# dab_mainboard.net
KiCad netlist of a schematic drawn in EAGLE
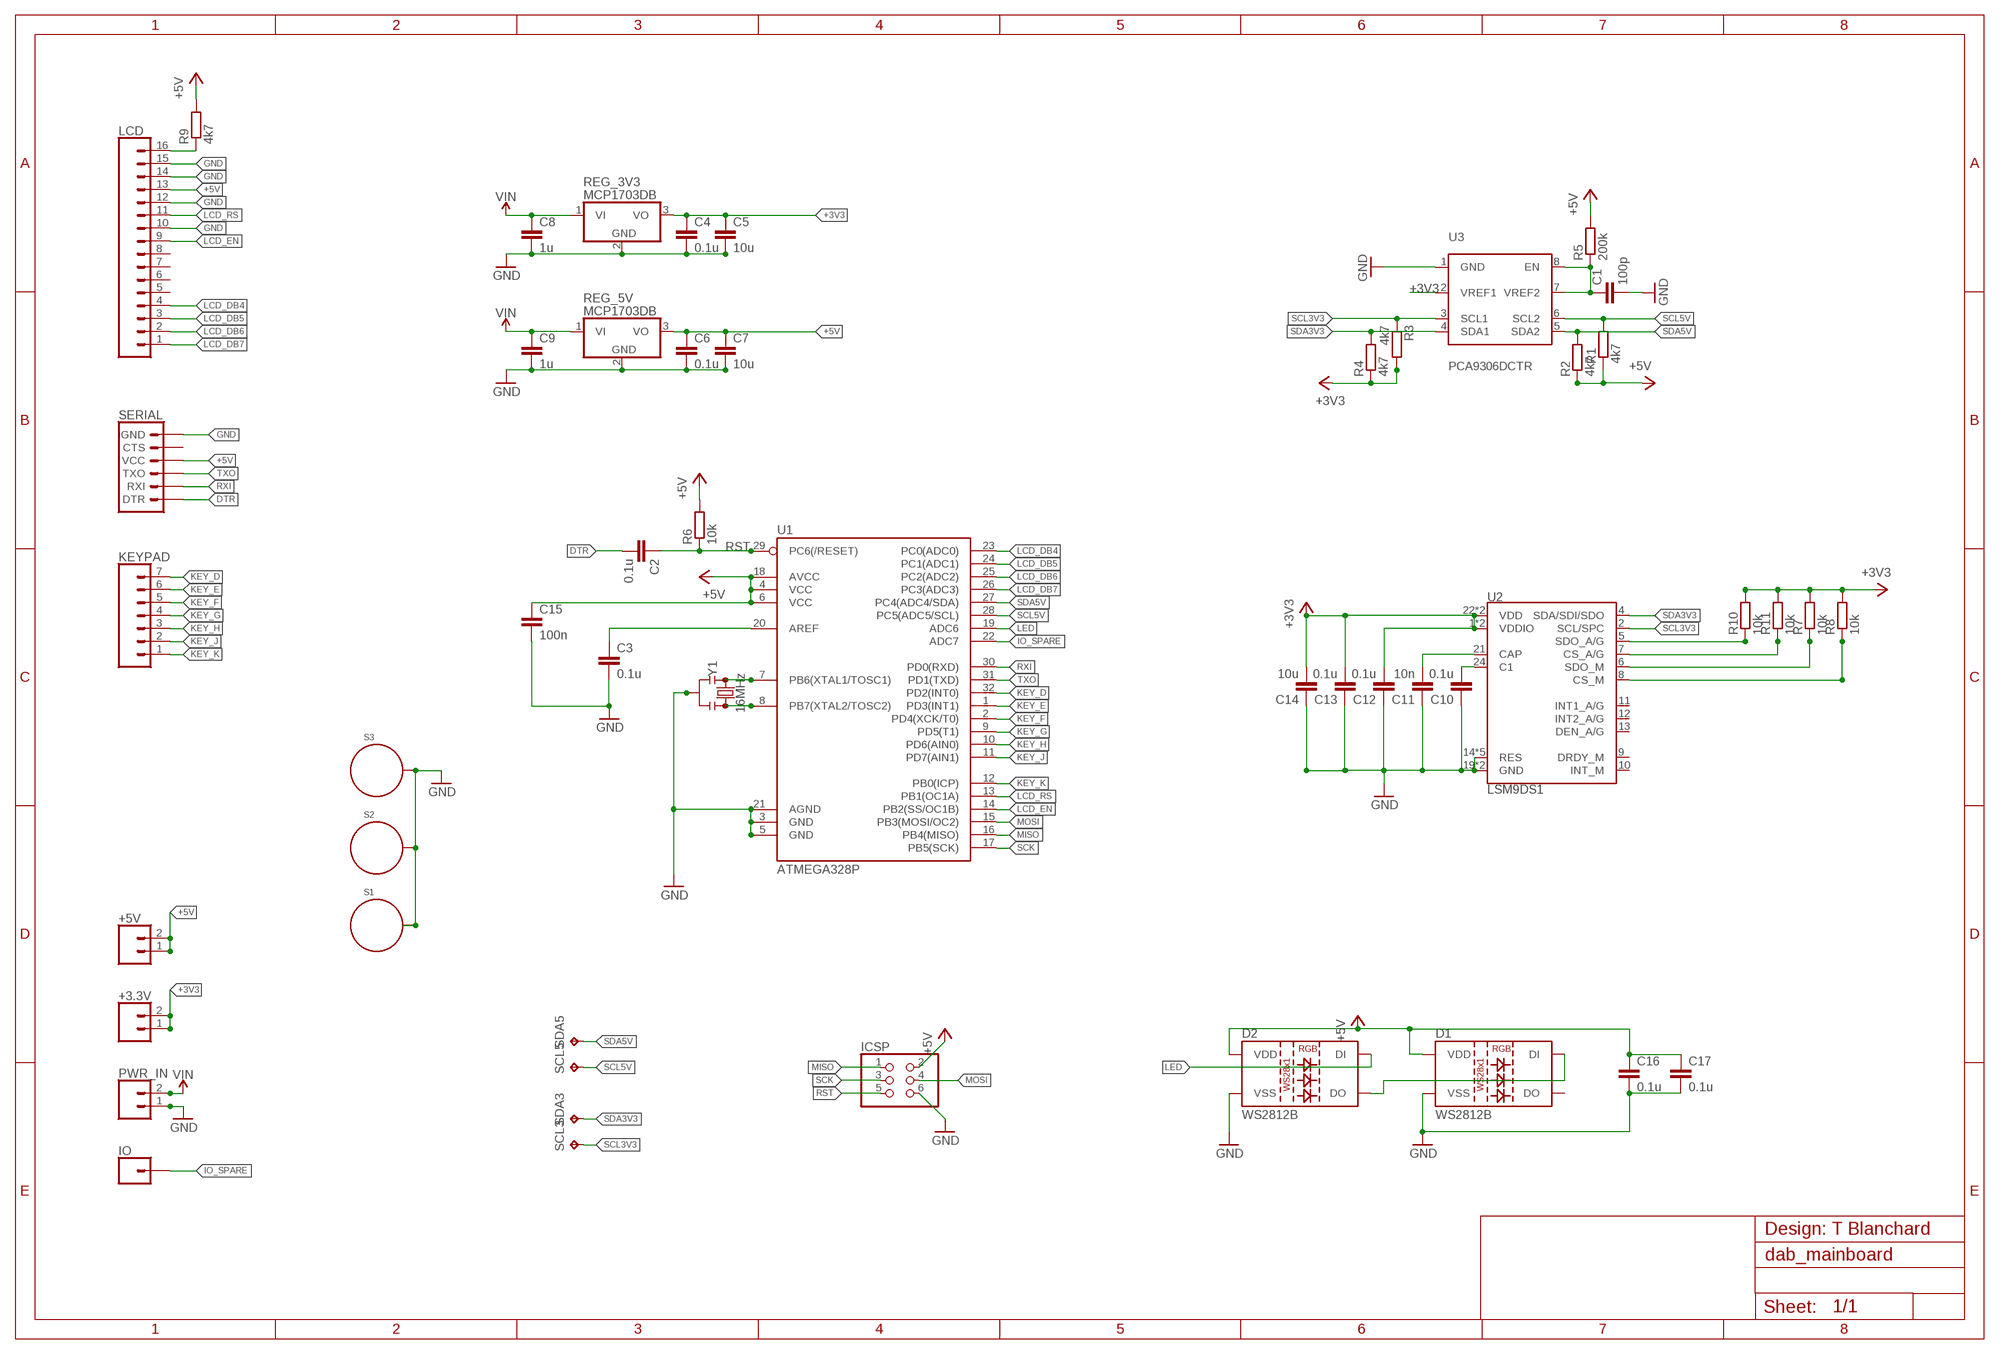
[diagram p0: schematic, sheet 1]

(export (version "E")
  (design (tool "Eeschema 10.0.6"))
  (components
    (comp (ref "+3.3V")
      (value "CONN_02")
      (footprint "eagle-import:1X02")
      (libsource (lib "eagle-import") (part "CONN_02"))
    )
    (comp (ref "+5V")
      (value "CONN_02")
      (footprint "eagle-import:1X02")
      (libsource (lib "eagle-import") (part "CONN_02"))
    )
    (comp (ref "C1")
      (value "100p")
      (footprint "eagle-import:C0603")
      (libsource (lib "eagle-import") (part "C-EUC0603"))
    )
    (comp (ref "C2")
      (value "0.1u")
      (footprint "eagle-import:C0603")
      (libsource (lib "eagle-import") (part "C-EUC0603"))
    )
    (comp (ref "C3")
      (value "0.1u")
      (footprint "eagle-import:C0603")
      (libsource (lib "eagle-import") (part "C-EUC0603"))
    )
    (comp (ref "C4")
      (value "0.1u")
      (footprint "eagle-import:C0603")
      (libsource (lib "eagle-import") (part "C-EUC0603"))
    )
    (comp (ref "C5")
      (value "10u")
      (footprint "eagle-import:C0805")
      (libsource (lib "eagle-import") (part "C-EUC0805"))
    )
    (comp (ref "C6")
      (value "0.1u")
      (footprint "eagle-import:C0603")
      (libsource (lib "eagle-import") (part "C-EUC0603"))
    )
    (comp (ref "C7")
      (value "10u")
      (footprint "eagle-import:C0805")
      (libsource (lib "eagle-import") (part "C-EUC0805"))
    )
    (comp (ref "C8")
      (value "1u")
      (footprint "eagle-import:C0603")
      (libsource (lib "eagle-import") (part "C-EUC0603"))
    )
    (comp (ref "C9")
      (value "1u")
      (footprint "eagle-import:C0603")
      (libsource (lib "eagle-import") (part "C-EUC0603"))
    )
    (comp (ref "C10")
      (value "0.1u")
      (footprint "eagle-import:C0603")
      (libsource (lib "eagle-import") (part "C-EUC0603"))
    )
    (comp (ref "C11")
      (value "10n")
      (footprint "eagle-import:C0603")
      (libsource (lib "eagle-import") (part "C-EUC0603"))
    )
    (comp (ref "C12")
      (value "0.1u")
      (footprint "eagle-import:C0603")
      (libsource (lib "eagle-import") (part "C-EUC0603"))
    )
    (comp (ref "C13")
      (value "0.1u")
      (footprint "eagle-import:C0603")
      (libsource (lib "eagle-import") (part "C-EUC0603"))
    )
    (comp (ref "C14")
      (value "10u")
      (footprint "eagle-import:C0603")
      (libsource (lib "eagle-import") (part "C-EUC0603"))
    )
    (comp (ref "C15")
      (value "100n")
      (footprint "eagle-import:C0603")
      (libsource (lib "eagle-import") (part "C-EUC0603"))
    )
    (comp (ref "C16")
      (value "0.1u")
      (footprint "eagle-import:C0603")
      (libsource (lib "eagle-import") (part "C-EUC0603"))
    )
    (comp (ref "C17")
      (value "0.1u")
      (footprint "eagle-import:C0603")
      (libsource (lib "eagle-import") (part "C-EUC0603"))
    )
    (comp (ref "D1")
      (value "WS2812B")
      (footprint "eagle-import:WS2812B")
      (libsource (lib "eagle-import") (part "WS2812B"))
    )
    (comp (ref "D2")
      (value "WS2812B")
      (footprint "eagle-import:WS2812B")
      (libsource (lib "eagle-import") (part "WS2812B"))
    )
    (comp (ref "ICSP")
      (value "PINHD-2X3")
      (footprint "eagle-import:2X03")
      (libsource (lib "eagle-import") (part "PINHD-2X3"))
    )
    (comp (ref "IO")
      (value "CONN_01")
      (footprint "eagle-import:1X01")
      (libsource (lib "eagle-import") (part "CONN_01"))
    )
    (comp (ref "KEYPAD")
      (value "CONN_07")
      (footprint "eagle-import:1X07")
      (libsource (lib "eagle-import") (part "CONN_07"))
    )
    (comp (ref "LCD")
      (value "CONN_16")
      (footprint "eagle-import:1X16")
      (libsource (lib "eagle-import") (part "CONN_16"))
    )
    (comp (ref "PWR_IN")
      (value "CONN_02")
      (footprint "eagle-import:1X02")
      (libsource (lib "eagle-import") (part "CONN_02"))
    )
    (comp (ref "R1")
      (value "4k7")
      (footprint "eagle-import:R0603")
      (libsource (lib "eagle-import") (part "R-EU_R0603"))
    )
    (comp (ref "R2")
      (value "4k7")
      (footprint "eagle-import:R0603")
      (libsource (lib "eagle-import") (part "R-EU_R0603"))
    )
    (comp (ref "R3")
      (value "4k7")
      (footprint "eagle-import:R0603")
      (libsource (lib "eagle-import") (part "R-EU_R0603"))
    )
    (comp (ref "R4")
      (value "4k7")
      (footprint "eagle-import:R0603")
      (libsource (lib "eagle-import") (part "R-EU_R0603"))
    )
    (comp (ref "R5")
      (value "200k")
      (footprint "eagle-import:R0603")
      (libsource (lib "eagle-import") (part "R-EU_R0603"))
    )
    (comp (ref "R6")
      (value "10k")
      (footprint "eagle-import:R0603")
      (libsource (lib "eagle-import") (part "R-EU_R0603"))
    )
    (comp (ref "R7")
      (value "10k")
      (footprint "eagle-import:R0603")
      (libsource (lib "eagle-import") (part "R-EU_R0603"))
    )
    (comp (ref "R8")
      (value "10k")
      (footprint "eagle-import:R0603")
      (libsource (lib "eagle-import") (part "R-EU_R0603"))
    )
    (comp (ref "R9")
      (value "4k7")
      (footprint "eagle-import:R0603")
      (libsource (lib "eagle-import") (part "R-EU_R0603"))
    )
    (comp (ref "R10")
      (value "10k")
      (footprint "eagle-import:R0603")
      (libsource (lib "eagle-import") (part "R-EU_R0603"))
    )
    (comp (ref "R11")
      (value "10k")
      (footprint "eagle-import:R0603")
      (libsource (lib "eagle-import") (part "R-EU_R0603"))
    )
    (comp (ref "REG_3V3")
      (value "MCP1703DB")
      (footprint "eagle-import:SOT223")
      (libsource (lib "eagle-import") (part "MCP1703DB"))
    )
    (comp (ref "REG_5V")
      (value "MCP1703DB")
      (footprint "eagle-import:SOT223")
      (libsource (lib "eagle-import") (part "MCP1703DB"))
    )
    (comp (ref "S1")
      (value "STANDOFF_ELECTRICAL")
      (footprint "eagle-import:STANDOFF-ELECTRICAL")
      (libsource (lib "eagle-import") (part "STANDOFF_ELECTRICAL"))
    )
    (comp (ref "S2")
      (value "STANDOFF_ELECTRICAL")
      (footprint "eagle-import:STANDOFF-ELECTRICAL")
      (libsource (lib "eagle-import") (part "STANDOFF_ELECTRICAL"))
    )
    (comp (ref "S3")
      (value "STANDOFF_ELECTRICAL")
      (footprint "eagle-import:STANDOFF-ELECTRICAL")
      (libsource (lib "eagle-import") (part "STANDOFF_ELECTRICAL"))
    )
    (comp (ref "SCL3")
      (value "TPTP08R")
      (footprint "eagle-import:TP08R")
      (libsource (lib "eagle-import") (part "TPTP08R"))
    )
    (comp (ref "SCL5")
      (value "TPTP08R")
      (footprint "eagle-import:TP08R")
      (libsource (lib "eagle-import") (part "TPTP08R"))
    )
    (comp (ref "SDA3")
      (value "TPTP08R")
      (footprint "eagle-import:TP08R")
      (libsource (lib "eagle-import") (part "TPTP08R"))
    )
    (comp (ref "SDA5")
      (value "TPTP08R")
      (footprint "eagle-import:TP08R")
      (libsource (lib "eagle-import") (part "TPTP08R"))
    )
    (comp (ref "SERIAL")
      (value "6_PIN_SERIAL_TARGETSILK")
      (footprint "eagle-import:6_PIN_SERIAL_TARGET_SIDE_W_SILK")
      (libsource (lib "eagle-import") (part "6_PIN_SERIAL_TARGETSILK"))
    )
    (comp (ref "U1")
      (value "ATMEGA328P")
      (footprint "eagle-import:TQFP32-08")
      (libsource (lib "eagle-import") (part "ATMEGA328P_TQFP"))
    )
    (comp (ref "U2")
      (value "LSM9DS1")
      (footprint "eagle-import:LGA-24-3.5X3")
      (libsource (lib "eagle-import") (part "LSM9DS1"))
    )
    (comp (ref "U3")
      (value "PCA9306DCTR")
      (footprint "eagle-import:SM8")
      (libsource (lib "eagle-import") (part "PCA9306DCTR"))
    )
    (comp (ref "Y1")
      (value "16MHz")
      (footprint "eagle-import:RESONATOR-SMD-3.2X1.3")
      (libsource (lib "eagle-import") (part "RESONATOR-16MHZSMD_3.2X1.3"))
    )
  )
  (nets
    (net (code "1") (name "+3V3") (class "Default")
      (node (ref "+3.3V") (pin "1") (pinfunction "1_1") (pintype "passive"))
      (node (ref "+3.3V") (pin "2") (pinfunction "2_2") (pintype "passive"))
      (node (ref "C12") (pin "2") (pinfunction "2_2") (pintype "passive"))
      (node (ref "C13") (pin "2") (pinfunction "2_2") (pintype "passive"))
      (node (ref "C14") (pin "2") (pinfunction "2_2") (pintype "passive"))
      (node (ref "C4") (pin "1") (pinfunction "1_1") (pintype "passive"))
      (node (ref "C5") (pin "1") (pinfunction "1_1") (pintype "passive"))
      (node (ref "R10") (pin "2") (pinfunction "2_2") (pintype "passive"))
      (node (ref "R11") (pin "2") (pinfunction "2_2") (pintype "passive"))
      (node (ref "R3") (pin "2") (pinfunction "2_2") (pintype "passive"))
      (node (ref "R4") (pin "1") (pinfunction "1_1") (pintype "passive"))
      (node (ref "R7") (pin "2") (pinfunction "2_2") (pintype "passive"))
      (node (ref "R8") (pin "2") (pinfunction "2_2") (pintype "passive"))
      (node (ref "REG_3V3") (pin "3") (pinfunction "VO_3") (pintype "passive"))
      (node (ref "U2") (pin "1") (pinfunction "VDDIO_1") (pintype "bidirectional"))
      (node (ref "U2") (pin "22") (pinfunction "VDD_22") (pintype "bidirectional"))
      (node (ref "U2") (pin "23") (pinfunction "VDD_23") (pintype "bidirectional"))
      (node (ref "U2") (pin "3") (pinfunction "VDDIO_3") (pintype "bidirectional"))
      (node (ref "U3") (pin "2") (pinfunction "VREF1_2") (pintype "power_in"))
    )
    (net (code "2") (name "+5V") (class "Default")
      (node (ref "+5V") (pin "1") (pinfunction "1_1") (pintype "passive"))
      (node (ref "+5V") (pin "2") (pinfunction "2_2") (pintype "passive"))
      (node (ref "C15") (pin "1") (pinfunction "1_1") (pintype "passive"))
      (node (ref "C16") (pin "1") (pinfunction "1_1") (pintype "passive"))
      (node (ref "C17") (pin "1") (pinfunction "1_1") (pintype "passive"))
      (node (ref "C6") (pin "1") (pinfunction "1_1") (pintype "passive"))
      (node (ref "C7") (pin "1") (pinfunction "1_1") (pintype "passive"))
      (node (ref "D1") (pin "1") (pinfunction "VDD_1") (pintype "bidirectional"))
      (node (ref "D2") (pin "1") (pinfunction "VDD_1") (pintype "bidirectional"))
      (node (ref "ICSP") (pin "2") (pinfunction "2_2") (pintype "passive"))
      (node (ref "LCD") (pin "13") (pinfunction "13_13") (pintype "passive"))
      (node (ref "R1") (pin "1") (pinfunction "1_1") (pintype "passive"))
      (node (ref "R2") (pin "1") (pinfunction "1_1") (pintype "passive"))
      (node (ref "R5") (pin "2") (pinfunction "2_2") (pintype "passive"))
      (node (ref "R6") (pin "2") (pinfunction "2_2") (pintype "passive"))
      (node (ref "R9") (pin "2") (pinfunction "2_2") (pintype "passive"))
      (node (ref "REG_5V") (pin "3") (pinfunction "VO_3") (pintype "passive"))
      (node (ref "SERIAL") (pin "P$4") (pinfunction "VCC_P$4") (pintype "passive"))
      (node (ref "U1") (pin "18") (pinfunction "AVCC_18") (pintype "bidirectional"))
      (node (ref "U1") (pin "4") (pinfunction "VCC_4") (pintype "bidirectional"))
      (node (ref "U1") (pin "6") (pinfunction "VCC_6") (pintype "bidirectional"))
    )
    (net (code "3") (name "DTR") (class "Default")
      (node (ref "C2") (pin "2") (pinfunction "2_2") (pintype "passive"))
      (node (ref "SERIAL") (pin "P$1") (pinfunction "DTR_P$1") (pintype "passive"))
    )
    (net (code "4") (name "GND") (class "Default")
      (node (ref "C1") (pin "2") (pinfunction "2_2") (pintype "passive"))
      (node (ref "C10") (pin "1") (pinfunction "1_1") (pintype "passive"))
      (node (ref "C11") (pin "1") (pinfunction "1_1") (pintype "passive"))
      (node (ref "C12") (pin "1") (pinfunction "1_1") (pintype "passive"))
      (node (ref "C13") (pin "1") (pinfunction "1_1") (pintype "passive"))
      (node (ref "C14") (pin "1") (pinfunction "1_1") (pintype "passive"))
      (node (ref "C15") (pin "2") (pinfunction "2_2") (pintype "passive"))
      (node (ref "C16") (pin "2") (pinfunction "2_2") (pintype "passive"))
      (node (ref "C17") (pin "2") (pinfunction "2_2") (pintype "passive"))
      (node (ref "C3") (pin "2") (pinfunction "2_2") (pintype "passive"))
      (node (ref "C4") (pin "2") (pinfunction "2_2") (pintype "passive"))
      (node (ref "C5") (pin "2") (pinfunction "2_2") (pintype "passive"))
      (node (ref "C6") (pin "2") (pinfunction "2_2") (pintype "passive"))
      (node (ref "C7") (pin "2") (pinfunction "2_2") (pintype "passive"))
      (node (ref "C8") (pin "2") (pinfunction "2_2") (pintype "passive"))
      (node (ref "C9") (pin "2") (pinfunction "2_2") (pintype "passive"))
      (node (ref "D1") (pin "3") (pinfunction "VSS_3") (pintype "bidirectional"))
      (node (ref "D2") (pin "3") (pinfunction "VSS_3") (pintype "bidirectional"))
      (node (ref "ICSP") (pin "6") (pinfunction "6_6") (pintype "passive"))
      (node (ref "LCD") (pin "10") (pinfunction "10_10") (pintype "passive"))
      (node (ref "LCD") (pin "12") (pinfunction "12_12") (pintype "passive"))
      (node (ref "LCD") (pin "14") (pinfunction "14_14") (pintype "passive"))
      (node (ref "LCD") (pin "15") (pinfunction "15_15") (pintype "passive"))
      (node (ref "PWR_IN") (pin "1") (pinfunction "1_1") (pintype "passive"))
      (node (ref "REG_3V3") (pin "2") (pinfunction "GND_2") (pintype "passive"))
      (node (ref "REG_5V") (pin "2") (pinfunction "GND_2") (pintype "passive"))
      (node (ref "S1") (pin "P1") (pinfunction "P$1_P1") (pintype "bidirectional"))
      (node (ref "S2") (pin "P1") (pinfunction "P$1_P1") (pintype "bidirectional"))
      (node (ref "S3") (pin "P1") (pinfunction "P$1_P1") (pintype "bidirectional"))
      (node (ref "SERIAL") (pin "P$6") (pinfunction "GND_P$6") (pintype "passive"))
      (node (ref "U1") (pin "21") (pinfunction "AGND_21") (pintype "bidirectional"))
      (node (ref "U1") (pin "3") (pinfunction "GND_3") (pintype "bidirectional"))
      (node (ref "U1") (pin "5") (pinfunction "GND_5") (pintype "bidirectional"))
      (node (ref "U2") (pin "14") (pinfunction "RES_14") (pintype "bidirectional"))
      (node (ref "U2") (pin "15") (pinfunction "RES_15") (pintype "bidirectional"))
      (node (ref "U2") (pin "16") (pinfunction "RES_16") (pintype "bidirectional"))
      (node (ref "U2") (pin "17") (pinfunction "RES_17") (pintype "bidirectional"))
      (node (ref "U2") (pin "18") (pinfunction "RES_18") (pintype "bidirectional"))
      (node (ref "U2") (pin "19") (pinfunction "GND_19") (pintype "bidirectional"))
      (node (ref "U2") (pin "20") (pinfunction "GND_20") (pintype "bidirectional"))
      (node (ref "U3") (pin "1") (pinfunction "GND_1") (pintype "power_in"))
      (node (ref "Y1") (pin "2") (pinfunction "2_2") (pintype "passive"))
    )
    (net (code "5") (name "IO_SPARE") (class "Default")
      (node (ref "IO") (pin "1") (pinfunction "1_1") (pintype "passive"))
      (node (ref "U1") (pin "22") (pinfunction "ADC7_22") (pintype "bidirectional"))
    )
    (net (code "6") (name "KEY_D") (class "Default")
      (node (ref "KEYPAD") (pin "7") (pinfunction "7_7") (pintype "passive"))
      (node (ref "U1") (pin "32") (pinfunction "PD2(INT0)_32") (pintype "bidirectional"))
    )
    (net (code "7") (name "KEY_E") (class "Default")
      (node (ref "KEYPAD") (pin "6") (pinfunction "6_6") (pintype "passive"))
      (node (ref "U1") (pin "1") (pinfunction "PD3(INT1)_1") (pintype "bidirectional"))
    )
    (net (code "8") (name "KEY_F") (class "Default")
      (node (ref "KEYPAD") (pin "5") (pinfunction "5_5") (pintype "passive"))
      (node (ref "U1") (pin "2") (pinfunction "PD4(XCK/T0)_2") (pintype "bidirectional"))
    )
    (net (code "9") (name "KEY_G") (class "Default")
      (node (ref "KEYPAD") (pin "4") (pinfunction "4_4") (pintype "passive"))
      (node (ref "U1") (pin "9") (pinfunction "PD5(T1)_9") (pintype "bidirectional"))
    )
    (net (code "10") (name "KEY_H") (class "Default")
      (node (ref "KEYPAD") (pin "3") (pinfunction "3_3") (pintype "passive"))
      (node (ref "U1") (pin "10") (pinfunction "PD6(AIN0)_10") (pintype "bidirectional"))
    )
    (net (code "11") (name "KEY_J") (class "Default")
      (node (ref "KEYPAD") (pin "2") (pinfunction "2_2") (pintype "passive"))
      (node (ref "U1") (pin "11") (pinfunction "PD7(AIN1)_11") (pintype "bidirectional"))
    )
    (net (code "12") (name "KEY_K") (class "Default")
      (node (ref "KEYPAD") (pin "1") (pinfunction "1_1") (pintype "passive"))
      (node (ref "U1") (pin "12") (pinfunction "PB0(ICP)_12") (pintype "bidirectional"))
    )
    (net (code "13") (name "LCD_DB4") (class "Default")
      (node (ref "LCD") (pin "4") (pinfunction "4_4") (pintype "passive"))
      (node (ref "U1") (pin "23") (pinfunction "PC0(ADC0)_23") (pintype "bidirectional"))
    )
    (net (code "14") (name "LCD_DB5") (class "Default")
      (node (ref "LCD") (pin "3") (pinfunction "3_3") (pintype "passive"))
      (node (ref "U1") (pin "24") (pinfunction "PC1(ADC1)_24") (pintype "bidirectional"))
    )
    (net (code "15") (name "LCD_DB6") (class "Default")
      (node (ref "LCD") (pin "2") (pinfunction "2_2") (pintype "passive"))
      (node (ref "U1") (pin "25") (pinfunction "PC2(ADC2)_25") (pintype "bidirectional"))
    )
    (net (code "16") (name "LCD_DB7") (class "Default")
      (node (ref "LCD") (pin "1") (pinfunction "1_1") (pintype "passive"))
      (node (ref "U1") (pin "26") (pinfunction "PC3(ADC3)_26") (pintype "bidirectional"))
    )
    (net (code "17") (name "LCD_EN") (class "Default")
      (node (ref "LCD") (pin "9") (pinfunction "9_9") (pintype "passive"))
      (node (ref "U1") (pin "14") (pinfunction "PB2(SS/OC1B)_14") (pintype "bidirectional"))
    )
    (net (code "18") (name "LCD_RS") (class "Default")
      (node (ref "LCD") (pin "11") (pinfunction "11_11") (pintype "passive"))
      (node (ref "U1") (pin "13") (pinfunction "PB1(OC1A)_13") (pintype "bidirectional"))
    )
    (net (code "19") (name "LED") (class "Default")
      (node (ref "D2") (pin "4") (pinfunction "DI_4") (pintype "bidirectional"))
      (node (ref "U1") (pin "19") (pinfunction "ADC6_19") (pintype "bidirectional"))
    )
    (net (code "20") (name "MISO") (class "Default")
      (node (ref "ICSP") (pin "1") (pinfunction "1_1") (pintype "passive"))
      (node (ref "U1") (pin "16") (pinfunction "PB4(MISO)_16") (pintype "bidirectional"))
    )
    (net (code "21") (name "MOSI") (class "Default")
      (node (ref "ICSP") (pin "4") (pinfunction "4_4") (pintype "passive"))
      (node (ref "U1") (pin "15") (pinfunction "PB3(MOSI/OC2)_15") (pintype "bidirectional"))
    )
    (net (code "22") (name "Net-(D1-DI)") (class "Default")
      (node (ref "D1") (pin "4") (pinfunction "DI_4") (pintype "bidirectional"))
      (node (ref "D2") (pin "2") (pinfunction "DO_2") (pintype "bidirectional"))
    )
    (net (code "23") (name "Net-(LCD-Pad16)") (class "Default")
      (node (ref "LCD") (pin "16") (pinfunction "16_16") (pintype "passive"))
      (node (ref "R9") (pin "1") (pinfunction "1_1") (pintype "passive"))
    )
    (net (code "24") (name "Net-(U1-AREF)") (class "Default")
      (node (ref "C3") (pin "1") (pinfunction "1_1") (pintype "passive"))
      (node (ref "U1") (pin "20") (pinfunction "AREF_20") (pintype "bidirectional"))
    )
    (net (code "25") (name "Net-(U1-PB6(XTAL1{slash}TOSC1))") (class "Default")
      (node (ref "U1") (pin "7") (pinfunction "PB6(XTAL1/TOSC1)_7") (pintype "bidirectional"))
      (node (ref "Y1") (pin "1") (pinfunction "1_1") (pintype "passive"))
    )
    (net (code "26") (name "Net-(U1-PB7(XTAL2{slash}TOSC2))") (class "Default")
      (node (ref "U1") (pin "8") (pinfunction "PB7(XTAL2/TOSC2)_8") (pintype "bidirectional"))
      (node (ref "Y1") (pin "3") (pinfunction "3_3") (pintype "passive"))
    )
    (net (code "27") (name "Net-(U2-C1)") (class "Default")
      (node (ref "C10") (pin "2") (pinfunction "2_2") (pintype "passive"))
      (node (ref "U2") (pin "24") (pinfunction "C1_24") (pintype "bidirectional"))
    )
    (net (code "28") (name "Net-(U2-CAP)") (class "Default")
      (node (ref "C11") (pin "2") (pinfunction "2_2") (pintype "passive"))
      (node (ref "U2") (pin "21") (pinfunction "CAP_21") (pintype "bidirectional"))
    )
    (net (code "29") (name "Net-(U2-CS_A{slash}G)") (class "Default")
      (node (ref "R11") (pin "1") (pinfunction "1_1") (pintype "passive"))
      (node (ref "U2") (pin "7") (pinfunction "CS_A/G_7") (pintype "bidirectional"))
    )
    (net (code "30") (name "Net-(U2-CS_M)") (class "Default")
      (node (ref "R8") (pin "1") (pinfunction "1_1") (pintype "passive"))
      (node (ref "U2") (pin "8") (pinfunction "CS_M_8") (pintype "bidirectional"))
    )
    (net (code "31") (name "Net-(U2-SDO_A{slash}G)") (class "Default")
      (node (ref "R10") (pin "1") (pinfunction "1_1") (pintype "passive"))
      (node (ref "U2") (pin "5") (pinfunction "SDO_A/G_5") (pintype "bidirectional"))
    )
    (net (code "32") (name "Net-(U2-SDO_M)") (class "Default")
      (node (ref "R7") (pin "1") (pinfunction "1_1") (pintype "passive"))
      (node (ref "U2") (pin "6") (pinfunction "SDO_M_6") (pintype "bidirectional"))
    )
    (net (code "33") (name "Net-(U3-EN)") (class "Default")
      (node (ref "C1") (pin "1") (pinfunction "1_1") (pintype "passive"))
      (node (ref "R5") (pin "1") (pinfunction "1_1") (pintype "passive"))
      (node (ref "U3") (pin "7") (pinfunction "VREF2_7") (pintype "power_in"))
      (node (ref "U3") (pin "8") (pinfunction "EN_8") (pintype "input"))
    )
    (net (code "34") (name "RST") (class "Default")
      (node (ref "C2") (pin "1") (pinfunction "1_1") (pintype "passive"))
      (node (ref "ICSP") (pin "5") (pinfunction "5_5") (pintype "passive"))
      (node (ref "R6") (pin "1") (pinfunction "1_1") (pintype "passive"))
      (node (ref "U1") (pin "29") (pinfunction "PC6(/RESET)_29") (pintype "bidirectional"))
    )
    (net (code "35") (name "RXI") (class "Default")
      (node (ref "SERIAL") (pin "P$3") (pinfunction "RXI_P$3") (pintype "passive"))
      (node (ref "U1") (pin "30") (pinfunction "PD0(RXD)_30") (pintype "bidirectional"))
    )
    (net (code "36") (name "SCK") (class "Default")
      (node (ref "ICSP") (pin "3") (pinfunction "3_3") (pintype "passive"))
      (node (ref "U1") (pin "17") (pinfunction "PB5(SCK)_17") (pintype "bidirectional"))
    )
    (net (code "37") (name "SCL3V3") (class "Default")
      (node (ref "R3") (pin "1") (pinfunction "1_1") (pintype "passive"))
      (node (ref "SCL3") (pin "TP") (pinfunction "TP_TP") (pintype "input"))
      (node (ref "U2") (pin "2") (pinfunction "SCL/SPC_2") (pintype "bidirectional"))
      (node (ref "U3") (pin "3") (pinfunction "SCL1_3") (pintype "bidirectional"))
    )
    (net (code "38") (name "SCL5V") (class "Default")
      (node (ref "R1") (pin "2") (pinfunction "2_2") (pintype "passive"))
      (node (ref "SCL5") (pin "TP") (pinfunction "TP_TP") (pintype "input"))
      (node (ref "U1") (pin "28") (pinfunction "PC5(ADC5/SCL)_28") (pintype "bidirectional"))
      (node (ref "U3") (pin "6") (pinfunction "SCL2_6") (pintype "bidirectional"))
    )
    (net (code "39") (name "SDA3V3") (class "Default")
      (node (ref "R4") (pin "2") (pinfunction "2_2") (pintype "passive"))
      (node (ref "SDA3") (pin "TP") (pinfunction "TP_TP") (pintype "input"))
      (node (ref "U2") (pin "4") (pinfunction "SDA/SDI/SDO_4") (pintype "bidirectional"))
      (node (ref "U3") (pin "4") (pinfunction "SDA1_4") (pintype "bidirectional"))
    )
    (net (code "40") (name "SDA5V") (class "Default")
      (node (ref "R2") (pin "2") (pinfunction "2_2") (pintype "passive"))
      (node (ref "SDA5") (pin "TP") (pinfunction "TP_TP") (pintype "input"))
      (node (ref "U1") (pin "27") (pinfunction "PC4(ADC4/SDA)_27") (pintype "bidirectional"))
      (node (ref "U3") (pin "5") (pinfunction "SDA2_5") (pintype "bidirectional"))
    )
    (net (code "41") (name "TXO") (class "Default")
      (node (ref "SERIAL") (pin "P$2") (pinfunction "TXO_P$2") (pintype "passive"))
      (node (ref "U1") (pin "31") (pinfunction "PD1(TXD)_31") (pintype "bidirectional"))
    )
    (net (code "42") (name "VIN") (class "Default")
      (node (ref "C8") (pin "1") (pinfunction "1_1") (pintype "passive"))
      (node (ref "C9") (pin "1") (pinfunction "1_1") (pintype "passive"))
      (node (ref "PWR_IN") (pin "2") (pinfunction "2_2") (pintype "passive"))
      (node (ref "REG_3V3") (pin "1") (pinfunction "VI_1") (pintype "input"))
      (node (ref "REG_5V") (pin "1") (pinfunction "VI_1") (pintype "input"))
    )
    (net (code "43") (name "unconnected-(D1-DO-Pad2)") (class "Default")
      (node (ref "D1") (pin "2") (pinfunction "DO_2") (pintype "bidirectional"))
    )
    (net (code "44") (name "unconnected-(LCD-Pad5)") (class "Default")
      (node (ref "LCD") (pin "5") (pinfunction "5_5") (pintype "passive"))
    )
    (net (code "45") (name "unconnected-(LCD-Pad6)") (class "Default")
      (node (ref "LCD") (pin "6") (pinfunction "6_6") (pintype "passive"))
    )
    (net (code "46") (name "unconnected-(LCD-Pad7)") (class "Default")
      (node (ref "LCD") (pin "7") (pinfunction "7_7") (pintype "passive"))
    )
    (net (code "47") (name "unconnected-(LCD-Pad8)") (class "Default")
      (node (ref "LCD") (pin "8") (pinfunction "8_8") (pintype "passive"))
    )
    (net (code "48") (name "unconnected-(SERIAL-CTS-PadP$5)") (class "Default")
      (node (ref "SERIAL") (pin "P$5") (pinfunction "CTS_P$5") (pintype "passive"))
    )
    (net (code "49") (name "unconnected-(U2-DEN_A{slash}G-Pad13)") (class "Default")
      (node (ref "U2") (pin "13") (pinfunction "DEN_A/G_13") (pintype "bidirectional"))
    )
    (net (code "50") (name "unconnected-(U2-DRDY_M-Pad9)") (class "Default")
      (node (ref "U2") (pin "9") (pinfunction "DRDY_M_9") (pintype "bidirectional"))
    )
    (net (code "51") (name "unconnected-(U2-INT1_A{slash}G-Pad11)") (class "Default")
      (node (ref "U2") (pin "11") (pinfunction "INT1_A/G_11") (pintype "bidirectional"))
    )
    (net (code "52") (name "unconnected-(U2-INT2_A{slash}G-Pad12)") (class "Default")
      (node (ref "U2") (pin "12") (pinfunction "INT2_A/G_12") (pintype "bidirectional"))
    )
    (net (code "53") (name "unconnected-(U2-INT_M-Pad10)") (class "Default")
      (node (ref "U2") (pin "10") (pinfunction "INT_M_10") (pintype "bidirectional"))
    )
  )
)
